# led.net
KiCad netlist of a schematic drawn in EAGLE
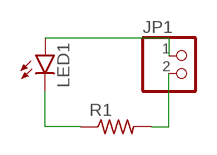
[diagram p0: schematic, sheet 1]

(export (version "E")
  (design (tool "Eeschema 10.0.6"))
  (components
    (comp (ref "JP1")
      (value "PINHD-1X2")
      (footprint "eagle-import:1X02")
      (libsource (lib "eagle-import") (part "PINHD-1X2"))
    )
    (comp (ref "LED1")
      (value "LED5MM")
      (footprint "eagle-import:LED5MM")
      (libsource (lib "eagle-import") (part "LED5MM"))
    )
    (comp (ref "R1")
      (value "R-US_0207/7")
      (footprint "eagle-import:0207_7")
      (libsource (lib "eagle-import") (part "R-US_0207/7"))
    )
  )
  (nets
    (net (code "1") (name "Net-(JP1-Pad1)") (class "Default")
      (node (ref "JP1") (pin "1") (pinfunction "1_1") (pintype "passive"))
      (node (ref "LED1") (pin "A") (pinfunction "A_A") (pintype "passive"))
    )
    (net (code "2") (name "Net-(JP1-Pad2)") (class "Default")
      (node (ref "JP1") (pin "2") (pinfunction "2_2") (pintype "passive"))
      (node (ref "R1") (pin "2") (pinfunction "2_2") (pintype "passive"))
    )
    (net (code "3") (name "Net-(LED1-C)") (class "Default")
      (node (ref "LED1") (pin "K") (pinfunction "C_K") (pintype "passive"))
      (node (ref "R1") (pin "1") (pinfunction "1_1") (pintype "passive"))
    )
  )
)
